# edisonLight.net
KiCad netlist of a schematic drawn in EAGLE
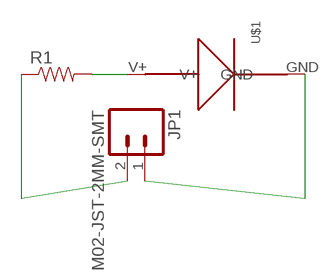
[diagram p0: schematic, sheet 1]

(export (version "E")
  (design (tool "Eeschema 10.0.6"))
  (components
    (comp (ref "JP1")
      (value "M02-JST-2MM-SMT")
      (footprint "eagle-import:JST-2-SMD")
      (libsource (lib "eagle-import") (part "M02-JST-2MM-SMT"))
    )
    (comp (ref "R1")
      (value "RESISTOR2010")
      (footprint "eagle-import:R2010")
      (libsource (lib "eagle-import") (part "RESISTOR2010"))
    )
    (comp (ref "U$1")
      (value "MYLEDDEV")
      (footprint "eagle-import:LTW-Z5630LED")
      (libsource (lib "eagle-import") (part "MYLEDDEV"))
    )
  )
  (nets
    (net (code "1") (name "Net-(JP1-1)") (class "Default")
      (node (ref "JP1") (pin "2") (pinfunction "1_2") (pintype "passive"))
      (node (ref "R1") (pin "1") (pinfunction "1_1") (pintype "passive"))
    )
    (net (code "2") (name "Net-(JP1-2)") (class "Default")
      (node (ref "JP1") (pin "1") (pinfunction "2_1") (pintype "passive"))
      (node (ref "U$1") (pin "GND") (pinfunction "GND_GND") (pintype "bidirectional"))
    )
    (net (code "3") (name "Net-(R1-Pad2)") (class "Default")
      (node (ref "R1") (pin "2") (pinfunction "2_2") (pintype "passive"))
      (node (ref "U$1") (pin "V+") (pinfunction "V+_V+") (pintype "bidirectional"))
    )
  )
)
